# uklad_zas_bateria.net
KiCad netlist of a schematic drawn in EAGLE
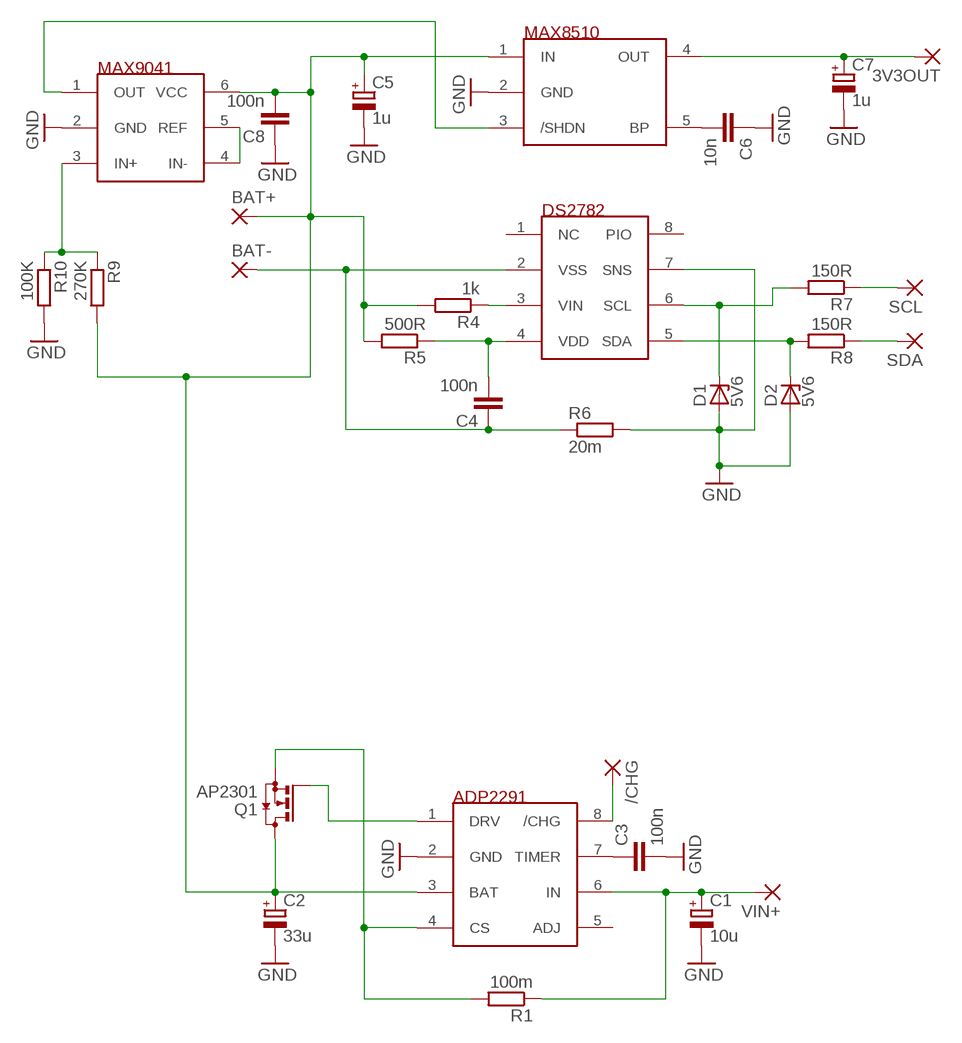
[diagram p0: schematic, sheet 1]

(export (version "E")
  (design (tool "Eeschema 10.0.6"))
  (components
    (comp (ref "/CHG")
      (value "2,54/0,8")
      (footprint "eagle-import:2,54_0,8")
      (libsource (lib "eagle-import") (part "2,54/0,8"))
    )
    (comp (ref "3V3OUT")
      (value "2,54/0,8")
      (footprint "eagle-import:2,54_0,8")
      (libsource (lib "eagle-import") (part "2,54/0,8"))
    )
    (comp (ref "BAT+")
      (value "2,54/0,8")
      (footprint "eagle-import:2,54_0,8")
      (libsource (lib "eagle-import") (part "2,54/0,8"))
    )
    (comp (ref "BAT-")
      (value "2,54/0,8")
      (footprint "eagle-import:2,54_0,8")
      (libsource (lib "eagle-import") (part "2,54/0,8"))
    )
    (comp (ref "C1")
      (value "10u")
      (footprint "eagle-import:E2-5")
      (libsource (lib "eagle-import") (part "CPOL-EUE2-5"))
    )
    (comp (ref "C2")
      (value "33u")
      (footprint "eagle-import:E2-5")
      (libsource (lib "eagle-import") (part "CPOL-EUE2-5"))
    )
    (comp (ref "C3")
      (value "100n")
      (footprint "eagle-import:C0805")
      (libsource (lib "eagle-import") (part "C-EUC0805"))
    )
    (comp (ref "C4")
      (value "100n")
      (footprint "eagle-import:C0805")
      (libsource (lib "eagle-import") (part "C-EUC0805"))
    )
    (comp (ref "C5")
      (value "1u")
      (footprint "eagle-import:E2-5")
      (libsource (lib "eagle-import") (part "CPOL-EUE2-5"))
    )
    (comp (ref "C6")
      (value "10n")
      (footprint "eagle-import:C0603")
      (libsource (lib "eagle-import") (part "C-EUC0603"))
    )
    (comp (ref "C7")
      (value "1u")
      (footprint "eagle-import:E2-5")
      (libsource (lib "eagle-import") (part "CPOL-EUE2-5"))
    )
    (comp (ref "C8")
      (value "100n")
      (footprint "eagle-import:C0805")
      (libsource (lib "eagle-import") (part "C-EUC0805"))
    )
    (comp (ref "D1")
      (value "5V6")
      (footprint "eagle-import:SOD80C")
      (libsource (lib "eagle-import") (part "ZENER-DIODESOD80C"))
    )
    (comp (ref "D2")
      (value "5V6")
      (footprint "eagle-import:SOD80C")
      (libsource (lib "eagle-import") (part "ZENER-DIODESOD80C"))
    )
    (comp (ref "Q1")
      (value "AP2301")
      (footprint "eagle-import:SOT23")
      (libsource (lib "eagle-import") (part "BSS123"))
    )
    (comp (ref "R1")
      (value "100m")
      (footprint "eagle-import:0207_10")
      (libsource (lib "eagle-import") (part "R-EU_0207/10"))
    )
    (comp (ref "R4")
      (value "1k")
      (footprint "eagle-import:M0805")
      (libsource (lib "eagle-import") (part "resistor_R-EU_M0805"))
    )
    (comp (ref "R5")
      (value "500R")
      (footprint "eagle-import:M0805")
      (libsource (lib "eagle-import") (part "resistor_R-EU_M0805"))
    )
    (comp (ref "R6")
      (value "20m")
      (footprint "eagle-import:M1206")
      (libsource (lib "eagle-import") (part "resistor_R-EU_M1206"))
    )
    (comp (ref "R7")
      (value "150R")
      (footprint "eagle-import:M0805")
      (libsource (lib "eagle-import") (part "resistor_R-EU_M0805"))
    )
    (comp (ref "R8")
      (value "150R")
      (footprint "eagle-import:M0805")
      (libsource (lib "eagle-import") (part "resistor_R-EU_M0805"))
    )
    (comp (ref "R9")
      (value "270K")
      (footprint "eagle-import:M0805")
      (libsource (lib "eagle-import") (part "resistor_R-EU_M0805"))
    )
    (comp (ref "R10")
      (value "100K")
      (footprint "eagle-import:M0805")
      (libsource (lib "eagle-import") (part "resistor_R-EU_M0805"))
    )
    (comp (ref "SCL")
      (value "2,54/0,8")
      (footprint "eagle-import:2,54_0,8")
      (libsource (lib "eagle-import") (part "2,54/0,8"))
    )
    (comp (ref "SDA")
      (value "2,54/0,8")
      (footprint "eagle-import:2,54_0,8")
      (libsource (lib "eagle-import") (part "2,54/0,8"))
    )
    (comp (ref "U$1")
      (value "ADP2291")
      (footprint "eagle-import:MSOP8")
      (libsource (lib "eagle-import") (part "ADP2291"))
    )
    (comp (ref "U$3")
      (value "DS2782")
      (footprint "eagle-import:TSSOP8")
      (libsource (lib "eagle-import") (part "DS2782"))
    )
    (comp (ref "U$4")
      (value "MAX8510")
      (footprint "eagle-import:SC70-5L")
      (libsource (lib "eagle-import") (part "MAX8510"))
    )
    (comp (ref "U$5")
      (value "MAX9041")
      (footprint "eagle-import:SOT23-6")
      (libsource (lib "eagle-import") (part "MAX9041"))
    )
    (comp (ref "VIN+")
      (value "2,54/0,8")
      (footprint "eagle-import:2,54_0,8")
      (libsource (lib "eagle-import") (part "2,54/0,8"))
    )
  )
  (nets
    (net (code "1") (name "GND") (class "Default")
      (node (ref "C1") (pin "-") (pinfunction "-_-") (pintype "passive"))
      (node (ref "C2") (pin "-") (pinfunction "-_-") (pintype "passive"))
      (node (ref "C3") (pin "2") (pinfunction "2_2") (pintype "passive"))
      (node (ref "C5") (pin "-") (pinfunction "-_-") (pintype "passive"))
      (node (ref "C6") (pin "1") (pinfunction "1_1") (pintype "passive"))
      (node (ref "C7") (pin "-") (pinfunction "-_-") (pintype "passive"))
      (node (ref "C8") (pin "1") (pinfunction "1_1") (pintype "passive"))
      (node (ref "D1") (pin "A") (pinfunction "A_A") (pintype "passive"))
      (node (ref "D2") (pin "A") (pinfunction "A_A") (pintype "passive"))
      (node (ref "R10") (pin "2") (pinfunction "2_2") (pintype "passive"))
      (node (ref "R6") (pin "2") (pinfunction "2_2") (pintype "passive"))
      (node (ref "U$1") (pin "2") (pinfunction "GND_2") (pintype "bidirectional"))
      (node (ref "U$3") (pin "7") (pinfunction "SNS_7") (pintype "bidirectional"))
      (node (ref "U$4") (pin "2") (pinfunction "GND_2") (pintype "bidirectional"))
      (node (ref "U$5") (pin "2") (pinfunction "GND_2") (pintype "bidirectional"))
    )
    (net (code "2") (name "Net-(/CHG-P)") (class "Default")
      (node (ref "/CHG") (pin "1") (pinfunction "P_1") (pintype "passive"))
      (node (ref "U$1") (pin "8") (pinfunction "/CHG_8") (pintype "bidirectional"))
    )
    (net (code "3") (name "Net-(3V3OUT-P)") (class "Default")
      (node (ref "3V3OUT") (pin "1") (pinfunction "P_1") (pintype "passive"))
      (node (ref "C7") (pin "+") (pinfunction "+_+") (pintype "passive"))
      (node (ref "U$4") (pin "4") (pinfunction "OUT_4") (pintype "bidirectional"))
    )
    (net (code "4") (name "Net-(BAT+-P)") (class "Default")
      (node (ref "BAT+") (pin "1") (pinfunction "P_1") (pintype "passive"))
      (node (ref "C2") (pin "+") (pinfunction "+_+") (pintype "passive"))
      (node (ref "C5") (pin "+") (pinfunction "+_+") (pintype "passive"))
      (node (ref "C8") (pin "2") (pinfunction "2_2") (pintype "passive"))
      (node (ref "Q1") (pin "3") (pinfunction "D_3") (pintype "passive"))
      (node (ref "R4") (pin "2") (pinfunction "2_2") (pintype "passive"))
      (node (ref "R5") (pin "2") (pinfunction "2_2") (pintype "passive"))
      (node (ref "R9") (pin "2") (pinfunction "2_2") (pintype "passive"))
      (node (ref "U$1") (pin "3") (pinfunction "BAT_3") (pintype "bidirectional"))
      (node (ref "U$4") (pin "1") (pinfunction "IN_1") (pintype "bidirectional"))
      (node (ref "U$5") (pin "6") (pinfunction "VCC_6") (pintype "bidirectional"))
    )
    (net (code "5") (name "Net-(BAT--P)") (class "Default")
      (node (ref "BAT-") (pin "1") (pinfunction "P_1") (pintype "passive"))
      (node (ref "C4") (pin "1") (pinfunction "1_1") (pintype "passive"))
      (node (ref "R6") (pin "1") (pinfunction "1_1") (pintype "passive"))
      (node (ref "U$3") (pin "2") (pinfunction "VSS_2") (pintype "bidirectional"))
    )
    (net (code "6") (name "Net-(Q1-G)") (class "Default")
      (node (ref "Q1") (pin "1") (pinfunction "G_1") (pintype "passive"))
      (node (ref "U$1") (pin "1") (pinfunction "DRV_1") (pintype "bidirectional"))
    )
    (net (code "7") (name "Net-(Q1-S)") (class "Default")
      (node (ref "Q1") (pin "2") (pinfunction "S_2") (pintype "passive"))
      (node (ref "R1") (pin "2") (pinfunction "2_2") (pintype "passive"))
      (node (ref "U$1") (pin "4") (pinfunction "CS_4") (pintype "bidirectional"))
    )
    (net (code "8") (name "Net-(SCL-P)") (class "Default")
      (node (ref "R7") (pin "1") (pinfunction "1_1") (pintype "passive"))
      (node (ref "SCL") (pin "1") (pinfunction "P_1") (pintype "passive"))
    )
    (net (code "9") (name "Net-(SDA-P)") (class "Default")
      (node (ref "R8") (pin "1") (pinfunction "1_1") (pintype "passive"))
      (node (ref "SDA") (pin "1") (pinfunction "P_1") (pintype "passive"))
    )
    (net (code "10") (name "Net-(U$1-IN)") (class "Default")
      (node (ref "C1") (pin "+") (pinfunction "+_+") (pintype "passive"))
      (node (ref "R1") (pin "1") (pinfunction "1_1") (pintype "passive"))
      (node (ref "U$1") (pin "6") (pinfunction "IN_6") (pintype "bidirectional"))
      (node (ref "VIN+") (pin "1") (pinfunction "P_1") (pintype "passive"))
    )
    (net (code "11") (name "Net-(U$1-TIMER)") (class "Default")
      (node (ref "C3") (pin "1") (pinfunction "1_1") (pintype "passive"))
      (node (ref "U$1") (pin "7") (pinfunction "TIMER_7") (pintype "bidirectional"))
    )
    (net (code "12") (name "Net-(U$3-SCL)") (class "Default")
      (node (ref "D1") (pin "C") (pinfunction "C_C") (pintype "passive"))
      (node (ref "R7") (pin "2") (pinfunction "2_2") (pintype "passive"))
      (node (ref "U$3") (pin "6") (pinfunction "SCL_6") (pintype "bidirectional"))
    )
    (net (code "13") (name "Net-(U$3-SDA)") (class "Default")
      (node (ref "D2") (pin "C") (pinfunction "C_C") (pintype "passive"))
      (node (ref "R8") (pin "2") (pinfunction "2_2") (pintype "passive"))
      (node (ref "U$3") (pin "5") (pinfunction "SDA_5") (pintype "bidirectional"))
    )
    (net (code "14") (name "Net-(U$3-VDD)") (class "Default")
      (node (ref "C4") (pin "2") (pinfunction "2_2") (pintype "passive"))
      (node (ref "R5") (pin "1") (pinfunction "1_1") (pintype "passive"))
      (node (ref "U$3") (pin "4") (pinfunction "VDD_4") (pintype "bidirectional"))
    )
    (net (code "15") (name "Net-(U$3-VIN)") (class "Default")
      (node (ref "R4") (pin "1") (pinfunction "1_1") (pintype "passive"))
      (node (ref "U$3") (pin "3") (pinfunction "VIN_3") (pintype "bidirectional"))
    )
    (net (code "16") (name "Net-(U$4-BP)") (class "Default")
      (node (ref "C6") (pin "2") (pinfunction "2_2") (pintype "passive"))
      (node (ref "U$4") (pin "5") (pinfunction "BP_5") (pintype "bidirectional"))
    )
    (net (code "17") (name "Net-(U$4-{slash}SHDN)") (class "Default")
      (node (ref "U$4") (pin "3") (pinfunction "/SHDN_3") (pintype "bidirectional"))
      (node (ref "U$5") (pin "1") (pinfunction "OUT_1") (pintype "bidirectional"))
    )
    (net (code "18") (name "Net-(U$5-IN+)") (class "Default")
      (node (ref "R10") (pin "1") (pinfunction "1_1") (pintype "passive"))
      (node (ref "R9") (pin "1") (pinfunction "1_1") (pintype "passive"))
      (node (ref "U$5") (pin "3") (pinfunction "IN+_3") (pintype "bidirectional"))
    )
    (net (code "19") (name "Net-(U$5-IN-)") (class "Default")
      (node (ref "U$5") (pin "4") (pinfunction "IN-_4") (pintype "bidirectional"))
      (node (ref "U$5") (pin "5") (pinfunction "REF_5") (pintype "bidirectional"))
    )
    (net (code "20") (name "unconnected-(U$1-ADJ-Pad5)") (class "Default")
      (node (ref "U$1") (pin "5") (pinfunction "ADJ_5") (pintype "bidirectional"))
    )
    (net (code "21") (name "unconnected-(U$3-NC-Pad1)") (class "Default")
      (node (ref "U$3") (pin "1") (pinfunction "NC_1") (pintype "bidirectional"))
    )
    (net (code "22") (name "unconnected-(U$3-PIO-Pad8)") (class "Default")
      (node (ref "U$3") (pin "8") (pinfunction "PIO_8") (pintype "bidirectional"))
    )
  )
)
